# QFN_triple_breakout.net
KiCad netlist of a schematic drawn in EAGLE
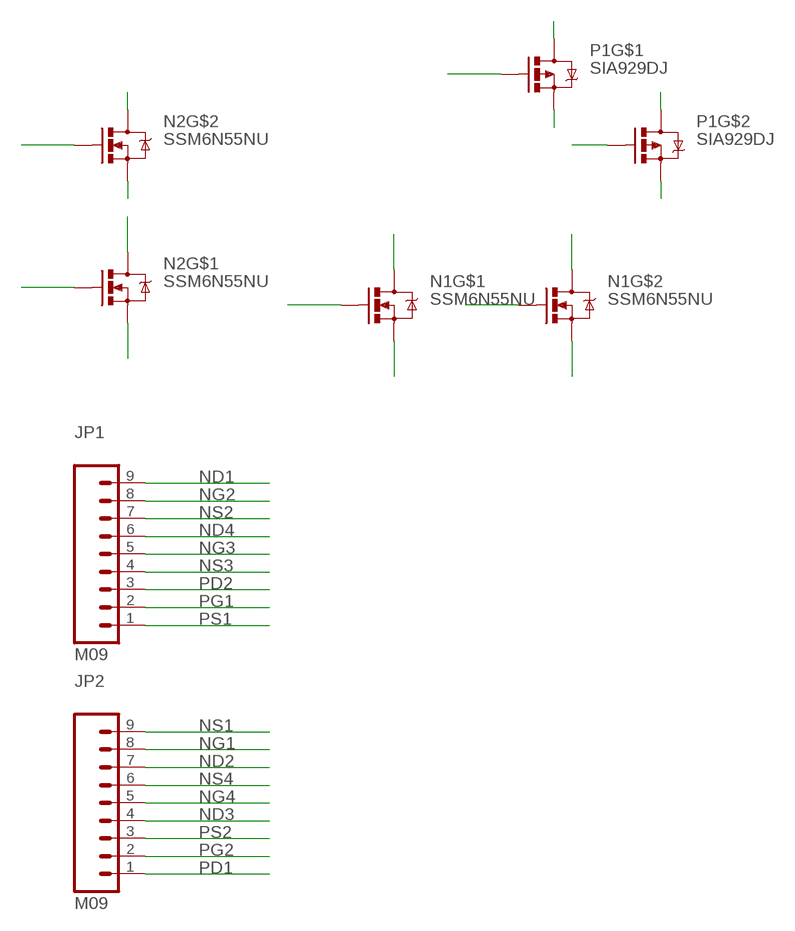
[diagram p0: schematic, sheet 1]

(export (version "E")
  (design (tool "Eeschema 10.0.6"))
  (components
    (comp (ref "JP1")
      (value "M09")
      (footprint "eagle-import:1X09")
      (libsource (lib "eagle-import") (part "M09"))
    )
    (comp (ref "JP2")
      (value "M09")
      (footprint "eagle-import:1X09")
      (libsource (lib "eagle-import") (part "M09"))
    )
    (comp (ref "N1")
      (value "SSM6N55NU")
      (footprint "eagle-import:UDFN6")
      (libsource (lib "eagle-import") (part "SSM6N55NU"))
    )
    (comp (ref "N2")
      (value "SSM6N55NU")
      (footprint "eagle-import:UDFN6")
      (libsource (lib "eagle-import") (part "SSM6N55NU"))
    )
    (comp (ref "P1")
      (value "SIA929DJ")
      (footprint "eagle-import:SC70-6L")
      (libsource (lib "eagle-import") (part "SIA929DJ"))
    )
  )
  (nets
    (net (code "1") (name "/ND1") (class "Default")
      (node (ref "JP1") (pin "9") (pinfunction "9_9") (pintype "passive"))
      (node (ref "N2") (pin "D2") (pinfunction "D_D2") (pintype "passive"))
      (node (ref "N2") (pin "D2$2") (pinfunction "D_D2$2") (pintype "passive"))
    )
    (net (code "2") (name "/ND2") (class "Default")
      (node (ref "JP2") (pin "7") (pinfunction "7_7") (pintype "passive"))
      (node (ref "N2") (pin "D1") (pinfunction "D_D1") (pintype "passive"))
      (node (ref "N2") (pin "D1$1") (pinfunction "D_D1$1") (pintype "passive"))
    )
    (net (code "3") (name "/ND3") (class "Default")
      (node (ref "JP2") (pin "4") (pinfunction "4_4") (pintype "passive"))
      (node (ref "N1") (pin "D1") (pinfunction "D_D1") (pintype "passive"))
      (node (ref "N1") (pin "D1$1") (pinfunction "D_D1$1") (pintype "passive"))
    )
    (net (code "4") (name "/ND4") (class "Default")
      (node (ref "JP1") (pin "6") (pinfunction "6_6") (pintype "passive"))
      (node (ref "N1") (pin "D2") (pinfunction "D_D2") (pintype "passive"))
      (node (ref "N1") (pin "D2$2") (pinfunction "D_D2$2") (pintype "passive"))
    )
    (net (code "5") (name "/NG1") (class "Default")
      (node (ref "JP2") (pin "8") (pinfunction "8_8") (pintype "passive"))
      (node (ref "N2") (pin "G2") (pinfunction "G_G2") (pintype "passive"))
    )
    (net (code "6") (name "/NG2") (class "Default")
      (node (ref "JP1") (pin "8") (pinfunction "8_8") (pintype "passive"))
      (node (ref "N2") (pin "G1") (pinfunction "G_G1") (pintype "passive"))
    )
    (net (code "7") (name "/NG3") (class "Default")
      (node (ref "JP1") (pin "5") (pinfunction "5_5") (pintype "passive"))
      (node (ref "N1") (pin "G1") (pinfunction "G_G1") (pintype "passive"))
    )
    (net (code "8") (name "/NG4") (class "Default")
      (node (ref "JP2") (pin "5") (pinfunction "5_5") (pintype "passive"))
      (node (ref "N1") (pin "G2") (pinfunction "G_G2") (pintype "passive"))
    )
    (net (code "9") (name "/NS1") (class "Default")
      (node (ref "JP2") (pin "9") (pinfunction "9_9") (pintype "passive"))
      (node (ref "N2") (pin "S2") (pinfunction "S_S2") (pintype "passive"))
    )
    (net (code "10") (name "/NS2") (class "Default")
      (node (ref "JP1") (pin "7") (pinfunction "7_7") (pintype "passive"))
      (node (ref "N2") (pin "S1") (pinfunction "S_S1") (pintype "passive"))
    )
    (net (code "11") (name "/NS3") (class "Default")
      (node (ref "JP1") (pin "4") (pinfunction "4_4") (pintype "passive"))
      (node (ref "N1") (pin "S1") (pinfunction "S_S1") (pintype "passive"))
    )
    (net (code "12") (name "/NS4") (class "Default")
      (node (ref "JP2") (pin "6") (pinfunction "6_6") (pintype "passive"))
      (node (ref "N1") (pin "S2") (pinfunction "S_S2") (pintype "passive"))
    )
    (net (code "13") (name "/PD1") (class "Default")
      (node (ref "JP2") (pin "1") (pinfunction "1_1") (pintype "passive"))
      (node (ref "P1") (pin "D1") (pinfunction "D_D1") (pintype "passive"))
      (node (ref "P1") (pin "D1$2") (pinfunction "D_D1$2") (pintype "passive"))
    )
    (net (code "14") (name "/PD2") (class "Default")
      (node (ref "JP1") (pin "3") (pinfunction "3_3") (pintype "passive"))
      (node (ref "P1") (pin "D2") (pinfunction "D_D2") (pintype "passive"))
      (node (ref "P1") (pin "D2$2") (pinfunction "D_D2$2") (pintype "passive"))
    )
    (net (code "15") (name "/PG1") (class "Default")
      (node (ref "JP1") (pin "2") (pinfunction "2_2") (pintype "passive"))
      (node (ref "P1") (pin "G1") (pinfunction "G_G1") (pintype "passive"))
    )
    (net (code "16") (name "/PG2") (class "Default")
      (node (ref "JP2") (pin "2") (pinfunction "2_2") (pintype "passive"))
      (node (ref "P1") (pin "G2") (pinfunction "G_G2") (pintype "passive"))
    )
    (net (code "17") (name "/PS1") (class "Default")
      (node (ref "JP1") (pin "1") (pinfunction "1_1") (pintype "passive"))
      (node (ref "P1") (pin "S1") (pinfunction "S_S1") (pintype "passive"))
    )
    (net (code "18") (name "/PS2") (class "Default")
      (node (ref "JP2") (pin "3") (pinfunction "3_3") (pintype "passive"))
      (node (ref "P1") (pin "S2") (pinfunction "S_S2") (pintype "passive"))
    )
  )
)
